# 14_-_mBUS-CAN.net
KiCad netlist of a schematic drawn in Altium Designer
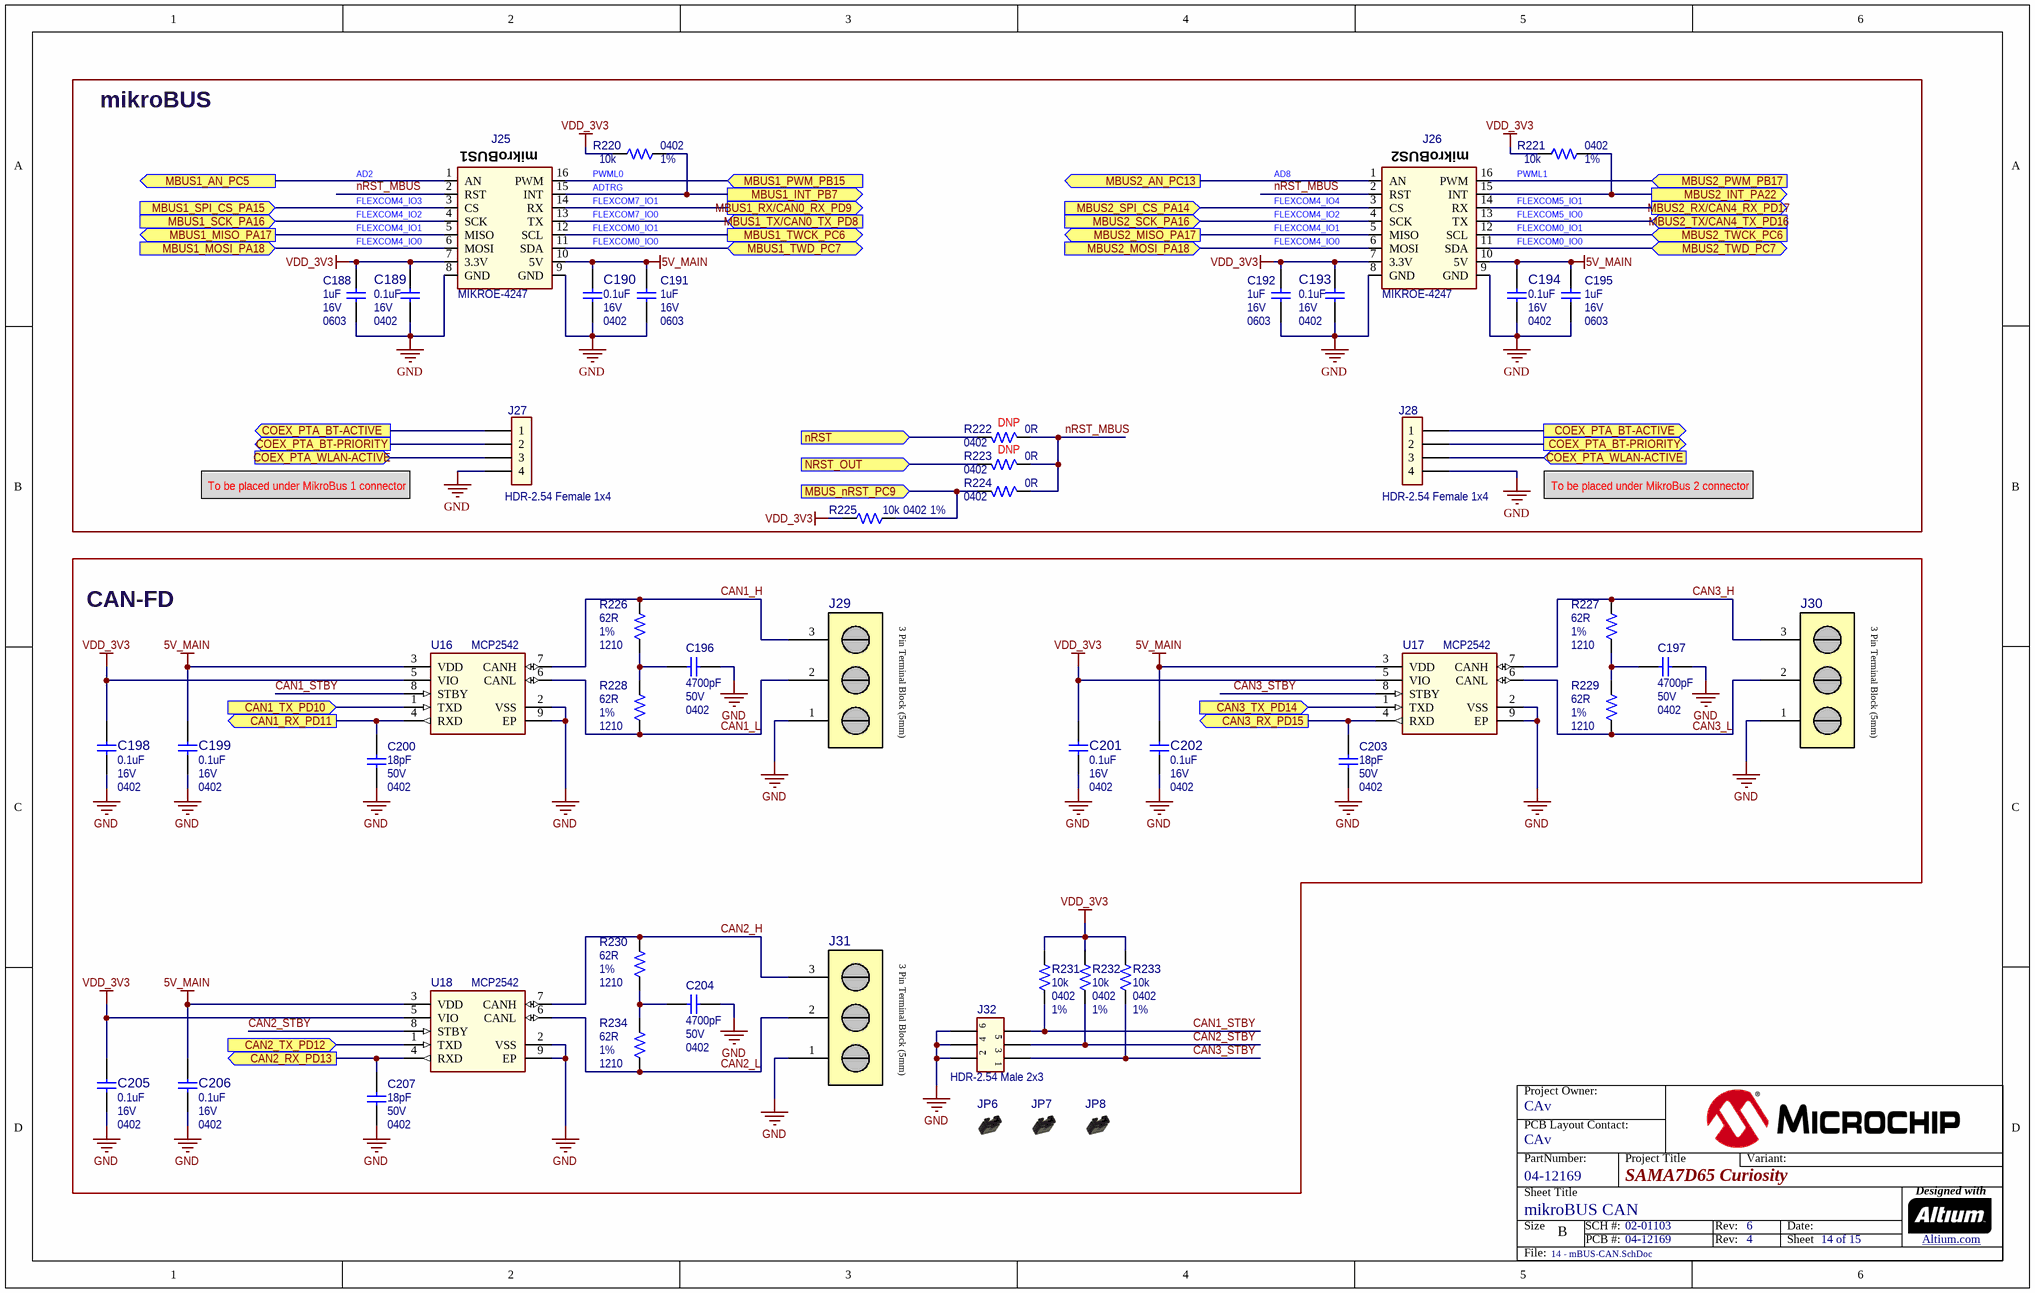
[diagram p0: 14 - mBUS-CAN.SchDoc]

(export (version "E")
  (design (tool "Eeschema 10.0.6"))
  (components
    (comp (ref "C188")
      (value "1uF")
      (footprint "CAP_C_0603")
      (fields
        (field (name "VOLTAGE") "16V")
        (field (name "PACKAGE") "0603")
        (field (name "TOLERANCE") "10%")
        (field (name "Comment") "Capacitor NP")
      )
      (libsource (lib "MCHP-CDB") (part "Capacitor NP"))
    )
    (comp (ref "C189")
      (value "0.1uF")
      (footprint "CAP_C_0402")
      (fields
        (field (name "VOLTAGE") "16V")
        (field (name "PACKAGE") "0402")
        (field (name "TOLERANCE") "10%")
        (field (name "Comment") "Capacitor NP")
        (field (name "OWNER") "Sompoch Loboonlert")
      )
      (libsource (lib "MCHP-CDB") (part "Capacitor NP"))
    )
    (comp (ref "C190")
      (value "0.1uF")
      (footprint "CAP_C_0402")
      (fields
        (field (name "VOLTAGE") "16V")
        (field (name "PACKAGE") "0402")
        (field (name "TOLERANCE") "10%")
        (field (name "Comment") "Capacitor NP")
        (field (name "OWNER") "Sompoch Loboonlert")
      )
      (libsource (lib "MCHP-CDB") (part "Capacitor NP"))
    )
    (comp (ref "C191")
      (value "1uF")
      (footprint "CAP_C_0603")
      (fields
        (field (name "VOLTAGE") "16V")
        (field (name "PACKAGE") "0603")
        (field (name "TOLERANCE") "10%")
        (field (name "Comment") "Capacitor NP")
      )
      (libsource (lib "MCHP-CDB") (part "Capacitor NP"))
    )
    (comp (ref "C192")
      (value "1uF")
      (footprint "CAP_C_0603")
      (fields
        (field (name "VOLTAGE") "16V")
        (field (name "PACKAGE") "0603")
        (field (name "TOLERANCE") "10%")
        (field (name "Comment") "Capacitor NP")
      )
      (libsource (lib "MCHP-CDB") (part "Capacitor NP"))
    )
    (comp (ref "C193")
      (value "0.1uF")
      (footprint "CAP_C_0402")
      (fields
        (field (name "VOLTAGE") "16V")
        (field (name "PACKAGE") "0402")
        (field (name "TOLERANCE") "10%")
        (field (name "Comment") "Capacitor NP")
        (field (name "OWNER") "Sompoch Loboonlert")
      )
      (libsource (lib "MCHP-CDB") (part "Capacitor NP"))
    )
    (comp (ref "C194")
      (value "0.1uF")
      (footprint "CAP_C_0402")
      (fields
        (field (name "VOLTAGE") "16V")
        (field (name "PACKAGE") "0402")
        (field (name "TOLERANCE") "10%")
        (field (name "Comment") "Capacitor NP")
        (field (name "OWNER") "Sompoch Loboonlert")
      )
      (libsource (lib "MCHP-CDB") (part "Capacitor NP"))
    )
    (comp (ref "C195")
      (value "1uF")
      (footprint "CAP_C_0603")
      (fields
        (field (name "VOLTAGE") "16V")
        (field (name "PACKAGE") "0603")
        (field (name "TOLERANCE") "10%")
        (field (name "Comment") "Capacitor NP")
      )
      (libsource (lib "MCHP-CDB") (part "Capacitor NP"))
    )
    (comp (ref "C196")
      (value "4700pF")
      (footprint "CAP_C_0402")
      (fields
        (field (name "VOLTAGE") "50V")
        (field (name "PACKAGE") "0402")
        (field (name "TOLERANCE") "10%")
        (field (name "Comment") "Capacitor NP")
        (field (name "OWNER") "Dragos Danaila")
      )
      (libsource (lib "MCHP-CDB") (part "Capacitor NP"))
    )
    (comp (ref "C197")
      (value "4700pF")
      (footprint "CAP_C_0402")
      (fields
        (field (name "VOLTAGE") "50V")
        (field (name "PACKAGE") "0402")
        (field (name "TOLERANCE") "10%")
        (field (name "Comment") "Capacitor NP")
        (field (name "OWNER") "Dragos Danaila")
      )
      (libsource (lib "MCHP-CDB") (part "Capacitor NP"))
    )
    (comp (ref "C198")
      (value "0.1uF")
      (footprint "CAP_C_0402")
      (fields
        (field (name "VOLTAGE") "16V")
        (field (name "PACKAGE") "0402")
        (field (name "TOLERANCE") "10%")
        (field (name "Comment") "Capacitor NP")
        (field (name "OWNER") "Sompoch Loboonlert")
      )
      (libsource (lib "MCHP-CDB") (part "Capacitor NP"))
    )
    (comp (ref "C199")
      (value "0.1uF")
      (footprint "CAP_C_0402")
      (fields
        (field (name "VOLTAGE") "16V")
        (field (name "PACKAGE") "0402")
        (field (name "TOLERANCE") "10%")
        (field (name "Comment") "Capacitor NP")
        (field (name "OWNER") "Sompoch Loboonlert")
      )
      (libsource (lib "MCHP-CDB") (part "Capacitor NP"))
    )
    (comp (ref "C200")
      (value "18pF")
      (footprint "CAP_C_0402")
      (fields
        (field (name "VOLTAGE") "50V")
        (field (name "PACKAGE") "0402")
        (field (name "TOLERANCE") "5%")
        (field (name "Comment") "Capacitor NP")
        (field (name "OWNER") "Tad Ahlvers")
      )
      (libsource (lib "MCHP-CDB") (part "Capacitor NP"))
    )
    (comp (ref "C201")
      (value "0.1uF")
      (footprint "CAP_C_0402")
      (fields
        (field (name "VOLTAGE") "16V")
        (field (name "PACKAGE") "0402")
        (field (name "TOLERANCE") "10%")
        (field (name "Comment") "Capacitor NP")
        (field (name "OWNER") "Sompoch Loboonlert")
      )
      (libsource (lib "MCHP-CDB") (part "Capacitor NP"))
    )
    (comp (ref "C202")
      (value "0.1uF")
      (footprint "CAP_C_0402")
      (fields
        (field (name "VOLTAGE") "16V")
        (field (name "PACKAGE") "0402")
        (field (name "TOLERANCE") "10%")
        (field (name "Comment") "Capacitor NP")
        (field (name "OWNER") "Sompoch Loboonlert")
      )
      (libsource (lib "MCHP-CDB") (part "Capacitor NP"))
    )
    (comp (ref "C203")
      (value "18pF")
      (footprint "CAP_C_0402")
      (fields
        (field (name "VOLTAGE") "50V")
        (field (name "PACKAGE") "0402")
        (field (name "TOLERANCE") "5%")
        (field (name "Comment") "Capacitor NP")
        (field (name "OWNER") "Tad Ahlvers")
      )
      (libsource (lib "MCHP-CDB") (part "Capacitor NP"))
    )
    (comp (ref "C204")
      (value "4700pF")
      (footprint "CAP_C_0402")
      (fields
        (field (name "VOLTAGE") "50V")
        (field (name "PACKAGE") "0402")
        (field (name "TOLERANCE") "10%")
        (field (name "Comment") "Capacitor NP")
        (field (name "OWNER") "Dragos Danaila")
      )
      (libsource (lib "MCHP-CDB") (part "Capacitor NP"))
    )
    (comp (ref "C205")
      (value "0.1uF")
      (footprint "CAP_C_0402")
      (fields
        (field (name "VOLTAGE") "16V")
        (field (name "PACKAGE") "0402")
        (field (name "TOLERANCE") "10%")
        (field (name "Comment") "Capacitor NP")
        (field (name "OWNER") "Sompoch Loboonlert")
      )
      (libsource (lib "MCHP-CDB") (part "Capacitor NP"))
    )
    (comp (ref "C206")
      (value "0.1uF")
      (footprint "CAP_C_0402")
      (fields
        (field (name "VOLTAGE") "16V")
        (field (name "PACKAGE") "0402")
        (field (name "TOLERANCE") "10%")
        (field (name "Comment") "Capacitor NP")
        (field (name "OWNER") "Sompoch Loboonlert")
      )
      (libsource (lib "MCHP-CDB") (part "Capacitor NP"))
    )
    (comp (ref "C207")
      (value "18pF")
      (footprint "CAP_C_0402")
      (fields
        (field (name "VOLTAGE") "50V")
        (field (name "PACKAGE") "0402")
        (field (name "TOLERANCE") "5%")
        (field (name "Comment") "Capacitor NP")
        (field (name "OWNER") "Tad Ahlvers")
      )
      (libsource (lib "MCHP-CDB") (part "Capacitor NP"))
    )
    (comp (ref "J25")
      (value "MIKROE-4247")
      (footprint "SOCKET_mikroBUS_F_2.54_2x8_V_25.4x21_original")
      (fields (field (name "Comment") "SOCKET mikroBUS HOST") (field (name "OWNER") "Dragos Danaila"))
      (libsource (lib "MCHP-CDB") (part "SOCKET mikroBUS HOST"))
    )
    (comp (ref "J26")
      (value "MIKROE-4247")
      (footprint "SOCKET_mikroBUS_F_2.54_2x8_V_25.4x21_original")
      (fields (field (name "Comment") "SOCKET mikroBUS HOST") (field (name "OWNER") "Dragos Danaila"))
      (libsource (lib "MCHP-CDB") (part "SOCKET mikroBUS HOST"))
    )
    (comp (ref "J27")
      (value "HDR-2.54 Female 1x4")
      (footprint "HDR_F_2.54_1x4")
      (fields
        (field (name "VOLTAGE") "250V")
        (field (name "Comment") "Header 1x4")
        (field (name "OWNER") "Ciprian Abramov")
      )
      (libsource (lib "MCHP-CDB") (part "Header 1x4"))
    )
    (comp (ref "J28")
      (value "HDR-2.54 Female 1x4")
      (footprint "HDR_F_2.54_1x4")
      (fields
        (field (name "VOLTAGE") "250V")
        (field (name "Comment") "Header 1x4")
        (field (name "OWNER") "Ciprian Abramov")
      )
      (libsource (lib "") (part "Header 1x4_1"))
    )
    (comp (ref "J29")
      (value "CON TERM BLK 1x3 TH Mount")
      (footprint "CON_TERMINAL_3.5_1x3_TH_RA_PHO_1985205")
      (fields (field (name "VOLTAGE") "400V") (field (name "OWNER") "Ciprian Abramov"))
      (libsource (lib "MCHP-CDB") (part "CON TERM BLK 1x3 TH Mount"))
    )
    (comp (ref "J30")
      (value "CON TERM BLK 1x3 TH Mount")
      (footprint "CON_TERMINAL_3.5_1x3_TH_RA_PHO_1985205")
      (fields (field (name "VOLTAGE") "400V") (field (name "OWNER") "Ciprian Abramov"))
      (libsource (lib "MCHP-CDB") (part "CON TERM BLK 1x3 TH Mount"))
    )
    (comp (ref "J31")
      (value "CON TERM BLK 1x3 TH Mount")
      (footprint "CON_TERMINAL_3.5_1x3_TH_RA_PHO_1985205")
      (fields (field (name "VOLTAGE") "400V") (field (name "OWNER") "Ciprian Abramov"))
      (libsource (lib "MCHP-CDB") (part "CON TERM BLK 1x3 TH Mount"))
    )
    (comp (ref "J32")
      (value "HDR-2.54 Male 2x3")
      (footprint "HDR_M_2.54_2x3")
      (fields (field (name "Comment") "Header 2x3"))
      (libsource (lib "MCHP-CDB") (part "Header 2x3"))
    )
    (comp (ref "JP6")
      (value "Jumper Mechanical")
      (footprint "Jumper_Mechanical")
      (fields (field (name "OWNER") "Narasimha Murthy"))
      (libsource (lib "MCHP-CDB") (part "Jumper Mechanical"))
    )
    (comp (ref "JP7")
      (value "Jumper Mechanical")
      (footprint "Jumper_Mechanical")
      (fields (field (name "OWNER") "Narasimha Murthy"))
      (libsource (lib "MCHP-CDB") (part "Jumper Mechanical"))
    )
    (comp (ref "JP8")
      (value "Jumper Mechanical")
      (footprint "Jumper_Mechanical")
      (fields (field (name "OWNER") "Narasimha Murthy"))
      (libsource (lib "MCHP-CDB") (part "Jumper Mechanical"))
    )
    (comp (ref "R220")
      (value "10k")
      (footprint "RES_C_0402")
      (description "Resistor")
      (fields
        (field (name "PACKAGE") "0402")
        (field (name "TOLERANCE") "1%")
        (field (name "VOLTAGE") "50V")
        (field (name "POWER") "1/10W")
        (field (name "OWNER") "Brent Lanphear")
      )
      (libsource (lib "MCHP-CDB") (part "Resistor"))
    )
    (comp (ref "R221")
      (value "10k")
      (footprint "RES_C_0402")
      (description "Resistor")
      (fields
        (field (name "PACKAGE") "0402")
        (field (name "TOLERANCE") "1%")
        (field (name "VOLTAGE") "50V")
        (field (name "POWER") "1/10W")
        (field (name "OWNER") "Brent Lanphear")
      )
      (libsource (lib "MCHP-CDB") (part "Resistor"))
    )
    (comp (ref "R222")
      (value "0R")
      (footprint "RES_C_0402")
      (description "Resistor")
      (fields
        (field (name "PACKAGE") "0402")
        (field (name "POWER") "1/16W")
        (field (name "POPULATED") "DNP")
        (field (name "OWNER") "Sompoch Loboonlert")
      )
      (libsource (lib "") (part "Resistor_1"))
    )
    (comp (ref "R223")
      (value "0R")
      (footprint "RES_C_0402")
      (description "Resistor")
      (fields
        (field (name "PACKAGE") "0402")
        (field (name "POWER") "1/16W")
        (field (name "POPULATED") "DNP")
        (field (name "OWNER") "Sompoch Loboonlert")
      )
      (libsource (lib "") (part "Resistor_1"))
    )
    (comp (ref "R224")
      (value "0R")
      (footprint "RES_C_0402")
      (description "Resistor")
      (fields
        (field (name "PACKAGE") "0402")
        (field (name "POWER") "1/16W")
        (field (name "OWNER") "Sompoch Loboonlert")
      )
      (libsource (lib "") (part "Resistor_1"))
    )
    (comp (ref "R225")
      (value "10k")
      (footprint "RES_C_0402")
      (description "Resistor")
      (fields
        (field (name "PACKAGE") "0402")
        (field (name "TOLERANCE") "1%")
        (field (name "VOLTAGE") "50V")
        (field (name "POWER") "1/10W")
        (field (name "OWNER") "Brent Lanphear")
      )
      (libsource (lib "MCHP-CDB") (part "Resistor"))
    )
    (comp (ref "R226")
      (value "62R")
      (footprint "RES_C_1210")
      (description "Resistor")
      (fields
        (field (name "PACKAGE") "1210")
        (field (name "TOLERANCE") "1%")
        (field (name "VOLTAGE") "200V")
        (field (name "POWER") "1/2W")
        (field (name "OWNER") "Dragos Danaila")
      )
      (libsource (lib "MCHP-CDB") (part "Resistor"))
    )
    (comp (ref "R227")
      (value "62R")
      (footprint "RES_C_1210")
      (description "Resistor")
      (fields
        (field (name "PACKAGE") "1210")
        (field (name "TOLERANCE") "1%")
        (field (name "VOLTAGE") "200V")
        (field (name "POWER") "1/2W")
        (field (name "OWNER") "Dragos Danaila")
      )
      (libsource (lib "MCHP-CDB") (part "Resistor"))
    )
    (comp (ref "R228")
      (value "62R")
      (footprint "RES_C_1210")
      (description "Resistor")
      (fields
        (field (name "PACKAGE") "1210")
        (field (name "TOLERANCE") "1%")
        (field (name "VOLTAGE") "200V")
        (field (name "POWER") "1/2W")
        (field (name "OWNER") "Dragos Danaila")
      )
      (libsource (lib "MCHP-CDB") (part "Resistor"))
    )
    (comp (ref "R229")
      (value "62R")
      (footprint "RES_C_1210")
      (description "Resistor")
      (fields
        (field (name "PACKAGE") "1210")
        (field (name "TOLERANCE") "1%")
        (field (name "VOLTAGE") "200V")
        (field (name "POWER") "1/2W")
        (field (name "OWNER") "Dragos Danaila")
      )
      (libsource (lib "MCHP-CDB") (part "Resistor"))
    )
    (comp (ref "R230")
      (value "62R")
      (footprint "RES_C_1210")
      (description "Resistor")
      (fields
        (field (name "PACKAGE") "1210")
        (field (name "TOLERANCE") "1%")
        (field (name "VOLTAGE") "200V")
        (field (name "POWER") "1/2W")
        (field (name "OWNER") "Dragos Danaila")
      )
      (libsource (lib "MCHP-CDB") (part "Resistor"))
    )
    (comp (ref "R231")
      (value "10k")
      (footprint "RES_C_0402")
      (description "Resistor")
      (fields
        (field (name "PACKAGE") "0402")
        (field (name "TOLERANCE") "1%")
        (field (name "VOLTAGE") "50V")
        (field (name "POWER") "1/10W")
        (field (name "OWNER") "Brent Lanphear")
      )
      (libsource (lib "MCHP-CDB") (part "Resistor"))
    )
    (comp (ref "R232")
      (value "10k")
      (footprint "RES_C_0402")
      (description "Resistor")
      (fields
        (field (name "PACKAGE") "0402")
        (field (name "TOLERANCE") "1%")
        (field (name "VOLTAGE") "50V")
        (field (name "POWER") "1/10W")
        (field (name "OWNER") "Brent Lanphear")
      )
      (libsource (lib "MCHP-CDB") (part "Resistor"))
    )
    (comp (ref "R233")
      (value "10k")
      (footprint "RES_C_0402")
      (description "Resistor")
      (fields
        (field (name "PACKAGE") "0402")
        (field (name "TOLERANCE") "1%")
        (field (name "VOLTAGE") "50V")
        (field (name "POWER") "1/10W")
        (field (name "OWNER") "Brent Lanphear")
      )
      (libsource (lib "MCHP-CDB") (part "Resistor"))
    )
    (comp (ref "R234")
      (value "62R")
      (footprint "RES_C_1210")
      (description "Resistor")
      (fields
        (field (name "PACKAGE") "1210")
        (field (name "TOLERANCE") "1%")
        (field (name "VOLTAGE") "200V")
        (field (name "POWER") "1/2W")
        (field (name "OWNER") "Dragos Danaila")
      )
      (libsource (lib "MCHP-CDB") (part "Resistor"))
    )
    (comp (ref "U16")
      (value "MCP2542")
      (footprint "DFN-8_3x3_EP2.4X1.55")
      (fields (field (name "Comment") "MCP2542 DFN-8") (field (name "OWNER") "Ilie Galan"))
      (libsource (lib "MCHP-CDB") (part "MCP2542 DFN-8"))
    )
    (comp (ref "U17")
      (value "MCP2542")
      (footprint "DFN-8_3x3_EP2.4X1.55")
      (fields (field (name "Comment") "MCP2542 DFN-8") (field (name "OWNER") "Ilie Galan"))
      (libsource (lib "MCHP-CDB") (part "MCP2542 DFN-8"))
    )
    (comp (ref "U18")
      (value "MCP2542")
      (footprint "DFN-8_3x3_EP2.4X1.55")
      (fields (field (name "Comment") "MCP2542 DFN-8") (field (name "OWNER") "Ilie Galan"))
      (libsource (lib "MCHP-CDB") (part "MCP2542 DFN-8"))
    )
  )
  (nets
    (net (code "1") (name "/CAN1_H") (class "Default")
      (node (ref "J29") (pin "3") (pinfunction "3_3") (pintype "power_in"))
      (node (ref "R226") (pin "2") (pinfunction "2_2") (pintype "passive"))
      (node (ref "U16") (pin "7") (pinfunction "CANH_7") (pintype "bidirectional"))
    )
    (net (code "2") (name "/CAN1_L") (class "Default")
      (node (ref "J29") (pin "2") (pinfunction "2_2") (pintype "power_in"))
      (node (ref "R228") (pin "1") (pinfunction "1_1") (pintype "passive"))
      (node (ref "U16") (pin "6") (pinfunction "CANL_6") (pintype "bidirectional"))
    )
    (net (code "3") (name "/CAN1_RX_PD11") (class "Default")
      (node (ref "C200") (pin "2") (pinfunction "2_2") (pintype "passive"))
      (node (ref "U16") (pin "4") (pinfunction "RXD_4") (pintype "output"))
    )
    (net (code "4") (name "/CAN1_STBY") (class "Default")
      (node (ref "J32") (pin "5") (pinfunction "5_5") (pintype "passive"))
      (node (ref "R231") (pin "1") (pinfunction "1_1") (pintype "passive"))
      (node (ref "U16") (pin "8") (pinfunction "STBY_8") (pintype "input"))
    )
    (net (code "5") (name "/CAN1_TX_PD10") (class "Default")
      (node (ref "U16") (pin "1") (pinfunction "TXD_1") (pintype "input"))
    )
    (net (code "6") (name "/CAN2_H") (class "Default")
      (node (ref "J31") (pin "3") (pinfunction "3_3") (pintype "power_in"))
      (node (ref "R230") (pin "2") (pinfunction "2_2") (pintype "passive"))
      (node (ref "U18") (pin "7") (pinfunction "CANH_7") (pintype "bidirectional"))
    )
    (net (code "7") (name "/CAN2_L") (class "Default")
      (node (ref "J31") (pin "2") (pinfunction "2_2") (pintype "power_in"))
      (node (ref "R234") (pin "1") (pinfunction "1_1") (pintype "passive"))
      (node (ref "U18") (pin "6") (pinfunction "CANL_6") (pintype "bidirectional"))
    )
    (net (code "8") (name "/CAN2_RX_PD13") (class "Default")
      (node (ref "C207") (pin "2") (pinfunction "2_2") (pintype "passive"))
      (node (ref "U18") (pin "4") (pinfunction "RXD_4") (pintype "output"))
    )
    (net (code "9") (name "/CAN2_STBY") (class "Default")
      (node (ref "J32") (pin "3") (pinfunction "3_3") (pintype "passive"))
      (node (ref "R232") (pin "1") (pinfunction "1_1") (pintype "passive"))
      (node (ref "U18") (pin "8") (pinfunction "STBY_8") (pintype "input"))
    )
    (net (code "10") (name "/CAN2_TX_PD12") (class "Default")
      (node (ref "U18") (pin "1") (pinfunction "TXD_1") (pintype "input"))
    )
    (net (code "11") (name "/CAN3_H") (class "Default")
      (node (ref "J30") (pin "3") (pinfunction "3_3") (pintype "power_in"))
      (node (ref "R227") (pin "2") (pinfunction "2_2") (pintype "passive"))
      (node (ref "U17") (pin "7") (pinfunction "CANH_7") (pintype "bidirectional"))
    )
    (net (code "12") (name "/CAN3_L") (class "Default")
      (node (ref "J30") (pin "2") (pinfunction "2_2") (pintype "power_in"))
      (node (ref "R229") (pin "1") (pinfunction "1_1") (pintype "passive"))
      (node (ref "U17") (pin "6") (pinfunction "CANL_6") (pintype "bidirectional"))
    )
    (net (code "13") (name "/CAN3_RX_PD15") (class "Default")
      (node (ref "C203") (pin "2") (pinfunction "2_2") (pintype "passive"))
      (node (ref "U17") (pin "4") (pinfunction "RXD_4") (pintype "output"))
    )
    (net (code "14") (name "/CAN3_STBY") (class "Default")
      (node (ref "J32") (pin "1") (pinfunction "1_1") (pintype "passive"))
      (node (ref "R233") (pin "1") (pinfunction "1_1") (pintype "passive"))
      (node (ref "U17") (pin "8") (pinfunction "STBY_8") (pintype "input"))
    )
    (net (code "15") (name "/CAN3_TX_PD14") (class "Default")
      (node (ref "U17") (pin "1") (pinfunction "TXD_1") (pintype "input"))
    )
    (net (code "16") (name "/COEX_PTA_BT-ACTIVE") (class "Default")
      (node (ref "J27") (pin "1") (pinfunction "1_1") (pintype "passive"))
      (node (ref "J28") (pin "1") (pinfunction "1_1") (pintype "passive"))
    )
    (net (code "17") (name "/COEX_PTA_BT-PRIORITY") (class "Default")
      (node (ref "J27") (pin "2") (pinfunction "2_2") (pintype "passive"))
      (node (ref "J28") (pin "2") (pinfunction "2_2") (pintype "passive"))
    )
    (net (code "18") (name "/COEX_PTA_WLAN-ACTIVE") (class "Default")
      (node (ref "J27") (pin "3") (pinfunction "3_3") (pintype "passive"))
      (node (ref "J28") (pin "3") (pinfunction "3_3") (pintype "passive"))
    )
    (net (code "19") (name "/MBUS1_AN_PC5") (class "Default")
      (node (ref "J25") (pin "1") (pinfunction "AN_1") (pintype "passive"))
    )
    (net (code "20") (name "/MBUS1_INT_PB7") (class "Default")
      (node (ref "J25") (pin "15") (pinfunction "INT_15") (pintype "passive"))
      (node (ref "R220") (pin "1") (pinfunction "1_1") (pintype "passive"))
    )
    (net (code "21") (name "/MBUS1_MISO_PA17") (class "Default")
      (node (ref "J25") (pin "5") (pinfunction "MISO_5") (pintype "passive"))
    )
    (net (code "22") (name "/MBUS1_MOSI_PA18") (class "Default")
      (node (ref "J25") (pin "6") (pinfunction "MOSI_6") (pintype "passive"))
    )
    (net (code "23") (name "/MBUS1_PWM_PB15") (class "Default")
      (node (ref "J25") (pin "16") (pinfunction "PWM_16") (pintype "passive"))
    )
    (net (code "24") (name "/MBUS1_RX{slash}CAN0_RX_PD9") (class "Default")
      (node (ref "J25") (pin "14") (pinfunction "RX_14") (pintype "passive"))
    )
    (net (code "25") (name "/MBUS1_SCK_PA16") (class "Default")
      (node (ref "J25") (pin "4") (pinfunction "SCK_4") (pintype "passive"))
    )
    (net (code "26") (name "/MBUS1_SPI_CS_PA15") (class "Default")
      (node (ref "J25") (pin "3") (pinfunction "CS_3") (pintype "passive"))
    )
    (net (code "27") (name "/MBUS1_TWCK_PC6") (class "Default")
      (node (ref "J25") (pin "12") (pinfunction "SCL_12") (pintype "passive"))
    )
    (net (code "28") (name "/MBUS1_TWD_PC7") (class "Default")
      (node (ref "J25") (pin "11") (pinfunction "SDA_11") (pintype "passive"))
    )
    (net (code "29") (name "/MBUS1_TX{slash}CAN0_TX_PD8") (class "Default")
      (node (ref "J25") (pin "13") (pinfunction "TX_13") (pintype "passive"))
    )
    (net (code "30") (name "/MBUS2_AN_PC13") (class "Default")
      (node (ref "J26") (pin "1") (pinfunction "AN_1") (pintype "passive"))
    )
    (net (code "31") (name "/MBUS2_INT_PA22") (class "Default")
      (node (ref "J26") (pin "15") (pinfunction "INT_15") (pintype "passive"))
      (node (ref "R221") (pin "1") (pinfunction "1_1") (pintype "passive"))
    )
    (net (code "32") (name "/MBUS2_MISO_PA17") (class "Default")
      (node (ref "J26") (pin "5") (pinfunction "MISO_5") (pintype "passive"))
    )
    (net (code "33") (name "/MBUS2_MOSI_PA18") (class "Default")
      (node (ref "J26") (pin "6") (pinfunction "MOSI_6") (pintype "passive"))
    )
    (net (code "34") (name "/MBUS2_PWM_PB17") (class "Default")
      (node (ref "J26") (pin "16") (pinfunction "PWM_16") (pintype "passive"))
    )
    (net (code "35") (name "/MBUS2_RX{slash}CAN4_RX_PD17") (class "Default")
      (node (ref "J26") (pin "14") (pinfunction "RX_14") (pintype "passive"))
    )
    (net (code "36") (name "/MBUS2_SCK_PA16") (class "Default")
      (node (ref "J26") (pin "4") (pinfunction "SCK_4") (pintype "passive"))
    )
    (net (code "37") (name "/MBUS2_SPI_CS_PA14") (class "Default")
      (node (ref "J26") (pin "3") (pinfunction "CS_3") (pintype "passive"))
    )
    (net (code "38") (name "/MBUS2_TWCK_PC6") (class "Default")
      (node (ref "J26") (pin "12") (pinfunction "SCL_12") (pintype "passive"))
    )
    (net (code "39") (name "/MBUS2_TWD_PC7") (class "Default")
      (node (ref "J26") (pin "11") (pinfunction "SDA_11") (pintype "passive"))
    )
    (net (code "40") (name "/MBUS2_TX{slash}CAN4_TX_PD16") (class "Default")
      (node (ref "J26") (pin "13") (pinfunction "TX_13") (pintype "passive"))
    )
    (net (code "41") (name "/MBUS_nRST_PC9") (class "Default")
      (node (ref "R224") (pin "1") (pinfunction "1_1") (pintype "passive"))
      (node (ref "R225") (pin "1") (pinfunction "1_1") (pintype "passive"))
    )
    (net (code "42") (name "/NRST_OUT") (class "Default")
      (node (ref "R223") (pin "1") (pinfunction "1_1") (pintype "passive"))
    )
    (net (code "43") (name "/nRST") (class "Default")
      (node (ref "R222") (pin "1") (pinfunction "1_1") (pintype "passive"))
    )
    (net (code "44") (name "/nRST_MBUS") (class "Default")
      (node (ref "J25") (pin "2") (pinfunction "RST_2") (pintype "passive"))
      (node (ref "J26") (pin "2") (pinfunction "RST_2") (pintype "passive"))
      (node (ref "R222") (pin "2") (pinfunction "2_2") (pintype "passive"))
      (node (ref "R223") (pin "2") (pinfunction "2_2") (pintype "passive"))
      (node (ref "R224") (pin "2") (pinfunction "2_2") (pintype "passive"))
    )
    (net (code "45") (name "5V_MAIN") (class "Default")
      (node (ref "C190") (pin "2") (pinfunction "2_2") (pintype "passive"))
      (node (ref "C191") (pin "2") (pinfunction "2_2") (pintype "passive"))
      (node (ref "C194") (pin "2") (pinfunction "2_2") (pintype "passive"))
      (node (ref "C195") (pin "2") (pinfunction "2_2") (pintype "passive"))
      (node (ref "C199") (pin "1") (pinfunction "1_1") (pintype "passive"))
      (node (ref "C202") (pin "1") (pinfunction "1_1") (pintype "passive"))
      (node (ref "C206") (pin "1") (pinfunction "1_1") (pintype "passive"))
      (node (ref "J25") (pin "10") (pinfunction "5V_10") (pintype "passive"))
      (node (ref "J26") (pin "10") (pinfunction "5V_10") (pintype "passive"))
      (node (ref "U16") (pin "3") (pinfunction "VDD_3") (pintype "power_in"))
      (node (ref "U17") (pin "3") (pinfunction "VDD_3") (pintype "power_in"))
      (node (ref "U18") (pin "3") (pinfunction "VDD_3") (pintype "power_in"))
    )
    (net (code "46") (name "GND") (class "Default")
      (node (ref "C188") (pin "1") (pinfunction "1_1") (pintype "passive"))
      (node (ref "C189") (pin "1") (pinfunction "1_1") (pintype "passive"))
      (node (ref "C190") (pin "1") (pinfunction "1_1") (pintype "passive"))
      (node (ref "C191") (pin "1") (pinfunction "1_1") (pintype "passive"))
      (node (ref "C192") (pin "1") (pinfunction "1_1") (pintype "passive"))
      (node (ref "C193") (pin "1") (pinfunction "1_1") (pintype "passive"))
      (node (ref "C194") (pin "1") (pinfunction "1_1") (pintype "passive"))
      (node (ref "C195") (pin "1") (pinfunction "1_1") (pintype "passive"))
      (node (ref "C196") (pin "1") (pinfunction "1_1") (pintype "passive"))
      (node (ref "C197") (pin "1") (pinfunction "1_1") (pintype "passive"))
      (node (ref "C198") (pin "2") (pinfunction "2_2") (pintype "passive"))
      (node (ref "C199") (pin "2") (pinfunction "2_2") (pintype "passive"))
      (node (ref "C200") (pin "1") (pinfunction "1_1") (pintype "passive"))
      (node (ref "C201") (pin "2") (pinfunction "2_2") (pintype "passive"))
      (node (ref "C202") (pin "2") (pinfunction "2_2") (pintype "passive"))
      (node (ref "C203") (pin "1") (pinfunction "1_1") (pintype "passive"))
      (node (ref "C204") (pin "1") (pinfunction "1_1") (pintype "passive"))
      (node (ref "C205") (pin "2") (pinfunction "2_2") (pintype "passive"))
      (node (ref "C206") (pin "2") (pinfunction "2_2") (pintype "passive"))
      (node (ref "C207") (pin "1") (pinfunction "1_1") (pintype "passive"))
      (node (ref "J25") (pin "8") (pinfunction "GND_8") (pintype "passive"))
      (node (ref "J25") (pin "9") (pinfunction "GND_9") (pintype "passive"))
      (node (ref "J26") (pin "8") (pinfunction "GND_8") (pintype "passive"))
      (node (ref "J26") (pin "9") (pinfunction "GND_9") (pintype "passive"))
      (node (ref "J27") (pin "4") (pinfunction "4_4") (pintype "passive"))
      (node (ref "J28") (pin "4") (pinfunction "4_4") (pintype "passive"))
      (node (ref "J29") (pin "1") (pinfunction "1_1") (pintype "power_in"))
      (node (ref "J30") (pin "1") (pinfunction "1_1") (pintype "power_in"))
      (node (ref "J31") (pin "1") (pinfunction "1_1") (pintype "power_in"))
      (node (ref "J32") (pin "2") (pinfunction "2_2") (pintype "passive"))
      (node (ref "J32") (pin "4") (pinfunction "4_4") (pintype "passive"))
      (node (ref "J32") (pin "6") (pinfunction "6_6") (pintype "passive"))
      (node (ref "U16") (pin "2") (pinfunction "VSS_2") (pintype "power_in"))
      (node (ref "U16") (pin "9") (pinfunction "EP_9") (pintype "passive"))
      (node (ref "U17") (pin "2") (pinfunction "VSS_2") (pintype "power_in"))
      (node (ref "U17") (pin "9") (pinfunction "EP_9") (pintype "passive"))
      (node (ref "U18") (pin "2") (pinfunction "VSS_2") (pintype "power_in"))
      (node (ref "U18") (pin "9") (pinfunction "EP_9") (pintype "passive"))
    )
    (net (code "47") (name "Net-(C196-Pad2)") (class "Default")
      (node (ref "C196") (pin "2") (pinfunction "2_2") (pintype "passive"))
      (node (ref "R226") (pin "1") (pinfunction "1_1") (pintype "passive"))
      (node (ref "R228") (pin "2") (pinfunction "2_2") (pintype "passive"))
    )
    (net (code "48") (name "Net-(C197-Pad2)") (class "Default")
      (node (ref "C197") (pin "2") (pinfunction "2_2") (pintype "passive"))
      (node (ref "R227") (pin "1") (pinfunction "1_1") (pintype "passive"))
      (node (ref "R229") (pin "2") (pinfunction "2_2") (pintype "passive"))
    )
    (net (code "49") (name "Net-(C204-Pad2)") (class "Default")
      (node (ref "C204") (pin "2") (pinfunction "2_2") (pintype "passive"))
      (node (ref "R230") (pin "1") (pinfunction "1_1") (pintype "passive"))
      (node (ref "R234") (pin "2") (pinfunction "2_2") (pintype "passive"))
    )
    (net (code "50") (name "VDD_3V3") (class "Default")
      (node (ref "C188") (pin "2") (pinfunction "2_2") (pintype "passive"))
      (node (ref "C189") (pin "2") (pinfunction "2_2") (pintype "passive"))
      (node (ref "C192") (pin "2") (pinfunction "2_2") (pintype "passive"))
      (node (ref "C193") (pin "2") (pinfunction "2_2") (pintype "passive"))
      (node (ref "C198") (pin "1") (pinfunction "1_1") (pintype "passive"))
      (node (ref "C201") (pin "1") (pinfunction "1_1") (pintype "passive"))
      (node (ref "C205") (pin "1") (pinfunction "1_1") (pintype "passive"))
      (node (ref "J25") (pin "7") (pinfunction "3.3V_7") (pintype "passive"))
      (node (ref "J26") (pin "7") (pinfunction "3.3V_7") (pintype "passive"))
      (node (ref "R220") (pin "2") (pinfunction "2_2") (pintype "passive"))
      (node (ref "R221") (pin "2") (pinfunction "2_2") (pintype "passive"))
      (node (ref "R225") (pin "2") (pinfunction "2_2") (pintype "passive"))
      (node (ref "R231") (pin "2") (pinfunction "2_2") (pintype "passive"))
      (node (ref "R232") (pin "2") (pinfunction "2_2") (pintype "passive"))
      (node (ref "R233") (pin "2") (pinfunction "2_2") (pintype "passive"))
      (node (ref "U16") (pin "5") (pinfunction "VIO_5") (pintype "power_in"))
      (node (ref "U17") (pin "5") (pinfunction "VIO_5") (pintype "power_in"))
      (node (ref "U18") (pin "5") (pinfunction "VIO_5") (pintype "power_in"))
    )
  )
)
